# carrier.net
KiCad netlist of a schematic drawn in EAGLE
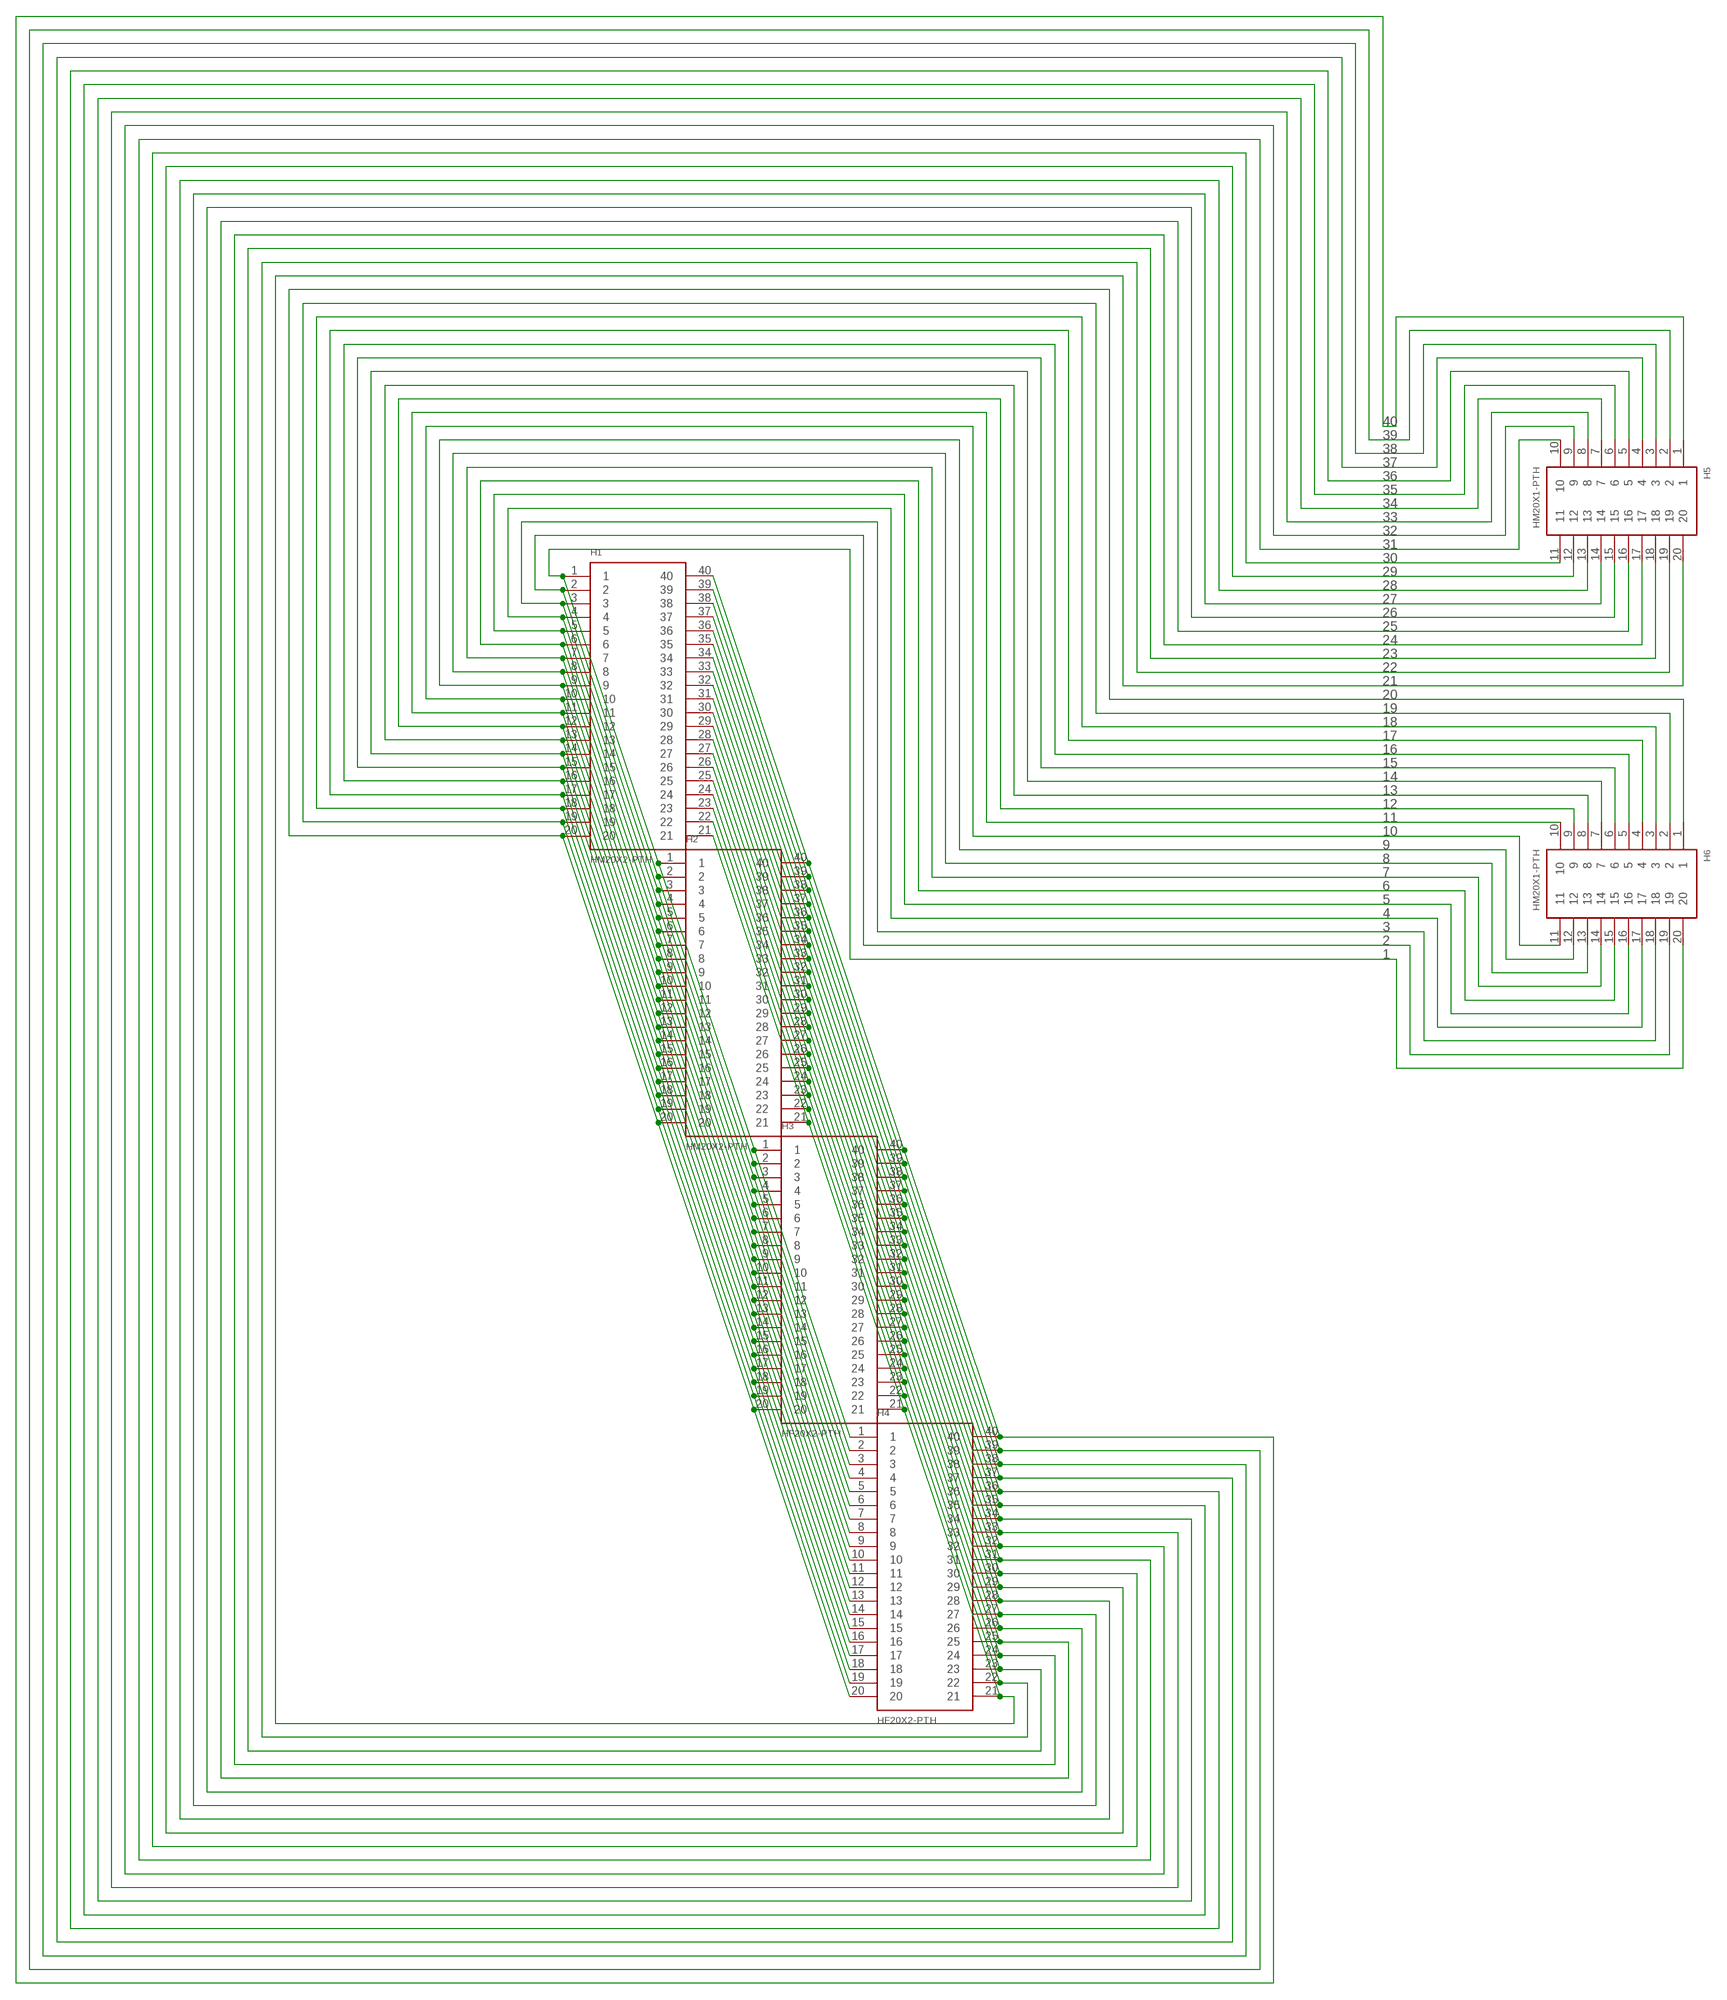
[diagram p0: schematic, sheet 1]

(export (version "E")
  (design (tool "Eeschema 10.0.6"))
  (components
    (comp (ref "H1")
      (value "HM20X2-PTH")
      (footprint "eagle-import:HM20X2-PTH")
      (libsource (lib "eagle-import") (part "HM20X2-PTH"))
    )
    (comp (ref "H2")
      (value "HM20X2-PTH")
      (footprint "eagle-import:HM20X2-PTH")
      (libsource (lib "eagle-import") (part "HM20X2-PTH"))
    )
    (comp (ref "H3")
      (value "HF20X2-PTH")
      (footprint "eagle-import:HF20X2-PTH")
      (libsource (lib "eagle-import") (part "HF20X2-PTH"))
    )
    (comp (ref "H4")
      (value "HF20X2-PTH")
      (footprint "eagle-import:HF20X2-PTH")
      (libsource (lib "eagle-import") (part "HF20X2-PTH"))
    )
    (comp (ref "H5")
      (value "HM20X1-PTH")
      (footprint "eagle-import:HM20X1-PTH")
      (libsource (lib "eagle-import") (part "HM20X1-PTH"))
    )
    (comp (ref "H6")
      (value "HM20X1-PTH")
      (footprint "eagle-import:HM20X1-PTH")
      (libsource (lib "eagle-import") (part "HM20X1-PTH"))
    )
  )
  (nets
    (net (code "1") (name "/1") (class "Default")
      (node (ref "H1") (pin "1") (pinfunction "1_1") (pintype "passive"))
      (node (ref "H2") (pin "1") (pinfunction "1_1") (pintype "passive"))
      (node (ref "H3") (pin "1") (pinfunction "1_1") (pintype "passive"))
      (node (ref "H4") (pin "1") (pinfunction "1_1") (pintype "passive"))
      (node (ref "H6") (pin "20") (pinfunction "20_20") (pintype "bidirectional"))
    )
    (net (code "2") (name "/2") (class "Default")
      (node (ref "H1") (pin "2") (pinfunction "2_2") (pintype "passive"))
      (node (ref "H2") (pin "2") (pinfunction "2_2") (pintype "passive"))
      (node (ref "H3") (pin "2") (pinfunction "2_2") (pintype "passive"))
      (node (ref "H4") (pin "2") (pinfunction "2_2") (pintype "passive"))
      (node (ref "H6") (pin "19") (pinfunction "19_19") (pintype "bidirectional"))
    )
    (net (code "3") (name "/3") (class "Default")
      (node (ref "H1") (pin "3") (pinfunction "3_3") (pintype "passive"))
      (node (ref "H2") (pin "3") (pinfunction "3_3") (pintype "passive"))
      (node (ref "H3") (pin "3") (pinfunction "3_3") (pintype "passive"))
      (node (ref "H4") (pin "3") (pinfunction "3_3") (pintype "passive"))
      (node (ref "H6") (pin "18") (pinfunction "18_18") (pintype "bidirectional"))
    )
    (net (code "4") (name "/4") (class "Default")
      (node (ref "H1") (pin "4") (pinfunction "4_4") (pintype "passive"))
      (node (ref "H2") (pin "4") (pinfunction "4_4") (pintype "passive"))
      (node (ref "H3") (pin "4") (pinfunction "4_4") (pintype "passive"))
      (node (ref "H4") (pin "4") (pinfunction "4_4") (pintype "passive"))
      (node (ref "H6") (pin "17") (pinfunction "17_17") (pintype "bidirectional"))
    )
    (net (code "5") (name "/5") (class "Default")
      (node (ref "H1") (pin "5") (pinfunction "5_5") (pintype "passive"))
      (node (ref "H2") (pin "5") (pinfunction "5_5") (pintype "passive"))
      (node (ref "H3") (pin "5") (pinfunction "5_5") (pintype "passive"))
      (node (ref "H4") (pin "5") (pinfunction "5_5") (pintype "passive"))
      (node (ref "H6") (pin "16") (pinfunction "16_16") (pintype "bidirectional"))
    )
    (net (code "6") (name "/6") (class "Default")
      (node (ref "H1") (pin "6") (pinfunction "6_6") (pintype "passive"))
      (node (ref "H2") (pin "6") (pinfunction "6_6") (pintype "passive"))
      (node (ref "H3") (pin "6") (pinfunction "6_6") (pintype "passive"))
      (node (ref "H4") (pin "6") (pinfunction "6_6") (pintype "passive"))
      (node (ref "H6") (pin "15") (pinfunction "15_15") (pintype "bidirectional"))
    )
    (net (code "7") (name "/7") (class "Default")
      (node (ref "H1") (pin "7") (pinfunction "7_7") (pintype "passive"))
      (node (ref "H2") (pin "7") (pinfunction "7_7") (pintype "passive"))
      (node (ref "H3") (pin "7") (pinfunction "7_7") (pintype "passive"))
      (node (ref "H4") (pin "7") (pinfunction "7_7") (pintype "passive"))
      (node (ref "H6") (pin "14") (pinfunction "14_14") (pintype "bidirectional"))
    )
    (net (code "8") (name "/8") (class "Default")
      (node (ref "H1") (pin "8") (pinfunction "8_8") (pintype "passive"))
      (node (ref "H2") (pin "8") (pinfunction "8_8") (pintype "passive"))
      (node (ref "H3") (pin "8") (pinfunction "8_8") (pintype "passive"))
      (node (ref "H4") (pin "8") (pinfunction "8_8") (pintype "passive"))
      (node (ref "H6") (pin "13") (pinfunction "13_13") (pintype "bidirectional"))
    )
    (net (code "9") (name "/9") (class "Default")
      (node (ref "H1") (pin "9") (pinfunction "9_9") (pintype "passive"))
      (node (ref "H2") (pin "9") (pinfunction "9_9") (pintype "passive"))
      (node (ref "H3") (pin "9") (pinfunction "9_9") (pintype "passive"))
      (node (ref "H4") (pin "9") (pinfunction "9_9") (pintype "passive"))
      (node (ref "H6") (pin "12") (pinfunction "12_12") (pintype "bidirectional"))
    )
    (net (code "10") (name "/10") (class "Default")
      (node (ref "H1") (pin "10") (pinfunction "10_10") (pintype "passive"))
      (node (ref "H2") (pin "10") (pinfunction "10_10") (pintype "passive"))
      (node (ref "H3") (pin "10") (pinfunction "10_10") (pintype "passive"))
      (node (ref "H4") (pin "10") (pinfunction "10_10") (pintype "passive"))
      (node (ref "H6") (pin "11") (pinfunction "11_11") (pintype "bidirectional"))
    )
    (net (code "11") (name "/11") (class "Default")
      (node (ref "H1") (pin "11") (pinfunction "11_11") (pintype "passive"))
      (node (ref "H2") (pin "11") (pinfunction "11_11") (pintype "passive"))
      (node (ref "H3") (pin "11") (pinfunction "11_11") (pintype "passive"))
      (node (ref "H4") (pin "11") (pinfunction "11_11") (pintype "passive"))
      (node (ref "H6") (pin "10") (pinfunction "10_10") (pintype "bidirectional"))
    )
    (net (code "12") (name "/12") (class "Default")
      (node (ref "H1") (pin "12") (pinfunction "12_12") (pintype "passive"))
      (node (ref "H2") (pin "12") (pinfunction "12_12") (pintype "passive"))
      (node (ref "H3") (pin "12") (pinfunction "12_12") (pintype "passive"))
      (node (ref "H4") (pin "12") (pinfunction "12_12") (pintype "passive"))
      (node (ref "H6") (pin "9") (pinfunction "9_9") (pintype "bidirectional"))
    )
    (net (code "13") (name "/13") (class "Default")
      (node (ref "H1") (pin "13") (pinfunction "13_13") (pintype "passive"))
      (node (ref "H2") (pin "13") (pinfunction "13_13") (pintype "passive"))
      (node (ref "H3") (pin "13") (pinfunction "13_13") (pintype "passive"))
      (node (ref "H4") (pin "13") (pinfunction "13_13") (pintype "passive"))
      (node (ref "H6") (pin "8") (pinfunction "8_8") (pintype "bidirectional"))
    )
    (net (code "14") (name "/14") (class "Default")
      (node (ref "H1") (pin "14") (pinfunction "14_14") (pintype "passive"))
      (node (ref "H2") (pin "14") (pinfunction "14_14") (pintype "passive"))
      (node (ref "H3") (pin "14") (pinfunction "14_14") (pintype "passive"))
      (node (ref "H4") (pin "14") (pinfunction "14_14") (pintype "passive"))
      (node (ref "H6") (pin "7") (pinfunction "7_7") (pintype "bidirectional"))
    )
    (net (code "15") (name "/15") (class "Default")
      (node (ref "H1") (pin "15") (pinfunction "15_15") (pintype "passive"))
      (node (ref "H2") (pin "15") (pinfunction "15_15") (pintype "passive"))
      (node (ref "H3") (pin "15") (pinfunction "15_15") (pintype "passive"))
      (node (ref "H4") (pin "15") (pinfunction "15_15") (pintype "passive"))
      (node (ref "H6") (pin "6") (pinfunction "6_6") (pintype "bidirectional"))
    )
    (net (code "16") (name "/16") (class "Default")
      (node (ref "H1") (pin "16") (pinfunction "16_16") (pintype "passive"))
      (node (ref "H2") (pin "16") (pinfunction "16_16") (pintype "passive"))
      (node (ref "H3") (pin "16") (pinfunction "16_16") (pintype "passive"))
      (node (ref "H4") (pin "16") (pinfunction "16_16") (pintype "passive"))
      (node (ref "H6") (pin "5") (pinfunction "5_5") (pintype "bidirectional"))
    )
    (net (code "17") (name "/17") (class "Default")
      (node (ref "H1") (pin "17") (pinfunction "17_17") (pintype "passive"))
      (node (ref "H2") (pin "17") (pinfunction "17_17") (pintype "passive"))
      (node (ref "H3") (pin "17") (pinfunction "17_17") (pintype "passive"))
      (node (ref "H4") (pin "17") (pinfunction "17_17") (pintype "passive"))
      (node (ref "H6") (pin "4") (pinfunction "4_4") (pintype "bidirectional"))
    )
    (net (code "18") (name "/18") (class "Default")
      (node (ref "H1") (pin "18") (pinfunction "18_18") (pintype "passive"))
      (node (ref "H2") (pin "18") (pinfunction "18_18") (pintype "passive"))
      (node (ref "H3") (pin "18") (pinfunction "18_18") (pintype "passive"))
      (node (ref "H4") (pin "18") (pinfunction "18_18") (pintype "passive"))
      (node (ref "H6") (pin "3") (pinfunction "3_3") (pintype "bidirectional"))
    )
    (net (code "19") (name "/19") (class "Default")
      (node (ref "H1") (pin "19") (pinfunction "19_19") (pintype "passive"))
      (node (ref "H2") (pin "19") (pinfunction "19_19") (pintype "passive"))
      (node (ref "H3") (pin "19") (pinfunction "19_19") (pintype "passive"))
      (node (ref "H4") (pin "19") (pinfunction "19_19") (pintype "passive"))
      (node (ref "H6") (pin "2") (pinfunction "2_2") (pintype "bidirectional"))
    )
    (net (code "20") (name "/20") (class "Default")
      (node (ref "H1") (pin "20") (pinfunction "20_20") (pintype "passive"))
      (node (ref "H2") (pin "20") (pinfunction "20_20") (pintype "passive"))
      (node (ref "H3") (pin "20") (pinfunction "20_20") (pintype "passive"))
      (node (ref "H4") (pin "20") (pinfunction "20_20") (pintype "passive"))
      (node (ref "H6") (pin "1") (pinfunction "1_1") (pintype "bidirectional"))
    )
    (net (code "21") (name "/21") (class "Default")
      (node (ref "H1") (pin "21") (pinfunction "21_21") (pintype "passive"))
      (node (ref "H2") (pin "21") (pinfunction "21_21") (pintype "passive"))
      (node (ref "H3") (pin "21") (pinfunction "21_21") (pintype "passive"))
      (node (ref "H4") (pin "21") (pinfunction "21_21") (pintype "passive"))
      (node (ref "H5") (pin "20") (pinfunction "20_20") (pintype "bidirectional"))
    )
    (net (code "22") (name "/22") (class "Default")
      (node (ref "H1") (pin "22") (pinfunction "22_22") (pintype "passive"))
      (node (ref "H2") (pin "22") (pinfunction "22_22") (pintype "passive"))
      (node (ref "H3") (pin "22") (pinfunction "22_22") (pintype "passive"))
      (node (ref "H4") (pin "22") (pinfunction "22_22") (pintype "passive"))
      (node (ref "H5") (pin "19") (pinfunction "19_19") (pintype "bidirectional"))
    )
    (net (code "23") (name "/23") (class "Default")
      (node (ref "H1") (pin "23") (pinfunction "23_23") (pintype "passive"))
      (node (ref "H2") (pin "23") (pinfunction "23_23") (pintype "passive"))
      (node (ref "H3") (pin "23") (pinfunction "23_23") (pintype "passive"))
      (node (ref "H4") (pin "23") (pinfunction "23_23") (pintype "passive"))
      (node (ref "H5") (pin "18") (pinfunction "18_18") (pintype "bidirectional"))
    )
    (net (code "24") (name "/24") (class "Default")
      (node (ref "H1") (pin "24") (pinfunction "24_24") (pintype "passive"))
      (node (ref "H2") (pin "24") (pinfunction "24_24") (pintype "passive"))
      (node (ref "H3") (pin "24") (pinfunction "24_24") (pintype "passive"))
      (node (ref "H4") (pin "24") (pinfunction "24_24") (pintype "passive"))
      (node (ref "H5") (pin "17") (pinfunction "17_17") (pintype "bidirectional"))
    )
    (net (code "25") (name "/25") (class "Default")
      (node (ref "H1") (pin "25") (pinfunction "25_25") (pintype "passive"))
      (node (ref "H2") (pin "25") (pinfunction "25_25") (pintype "passive"))
      (node (ref "H3") (pin "25") (pinfunction "25_25") (pintype "passive"))
      (node (ref "H4") (pin "25") (pinfunction "25_25") (pintype "passive"))
      (node (ref "H5") (pin "16") (pinfunction "16_16") (pintype "bidirectional"))
    )
    (net (code "26") (name "/26") (class "Default")
      (node (ref "H1") (pin "26") (pinfunction "26_26") (pintype "passive"))
      (node (ref "H2") (pin "26") (pinfunction "26_26") (pintype "passive"))
      (node (ref "H3") (pin "26") (pinfunction "26_26") (pintype "passive"))
      (node (ref "H4") (pin "26") (pinfunction "26_26") (pintype "passive"))
      (node (ref "H5") (pin "15") (pinfunction "15_15") (pintype "bidirectional"))
    )
    (net (code "27") (name "/27") (class "Default")
      (node (ref "H1") (pin "27") (pinfunction "27_27") (pintype "passive"))
      (node (ref "H2") (pin "27") (pinfunction "27_27") (pintype "passive"))
      (node (ref "H3") (pin "27") (pinfunction "27_27") (pintype "passive"))
      (node (ref "H4") (pin "27") (pinfunction "27_27") (pintype "passive"))
      (node (ref "H5") (pin "14") (pinfunction "14_14") (pintype "bidirectional"))
    )
    (net (code "28") (name "/28") (class "Default")
      (node (ref "H1") (pin "28") (pinfunction "28_28") (pintype "passive"))
      (node (ref "H2") (pin "28") (pinfunction "28_28") (pintype "passive"))
      (node (ref "H3") (pin "28") (pinfunction "28_28") (pintype "passive"))
      (node (ref "H4") (pin "28") (pinfunction "28_28") (pintype "passive"))
      (node (ref "H5") (pin "13") (pinfunction "13_13") (pintype "bidirectional"))
    )
    (net (code "29") (name "/29") (class "Default")
      (node (ref "H1") (pin "29") (pinfunction "29_29") (pintype "passive"))
      (node (ref "H2") (pin "29") (pinfunction "29_29") (pintype "passive"))
      (node (ref "H3") (pin "29") (pinfunction "29_29") (pintype "passive"))
      (node (ref "H4") (pin "29") (pinfunction "29_29") (pintype "passive"))
      (node (ref "H5") (pin "12") (pinfunction "12_12") (pintype "bidirectional"))
    )
    (net (code "30") (name "/30") (class "Default")
      (node (ref "H1") (pin "30") (pinfunction "30_30") (pintype "passive"))
      (node (ref "H2") (pin "30") (pinfunction "30_30") (pintype "passive"))
      (node (ref "H3") (pin "30") (pinfunction "30_30") (pintype "passive"))
      (node (ref "H4") (pin "30") (pinfunction "30_30") (pintype "passive"))
      (node (ref "H5") (pin "11") (pinfunction "11_11") (pintype "bidirectional"))
    )
    (net (code "31") (name "/31") (class "Default")
      (node (ref "H1") (pin "31") (pinfunction "31_31") (pintype "passive"))
      (node (ref "H2") (pin "31") (pinfunction "31_31") (pintype "passive"))
      (node (ref "H3") (pin "31") (pinfunction "31_31") (pintype "passive"))
      (node (ref "H4") (pin "31") (pinfunction "31_31") (pintype "passive"))
      (node (ref "H5") (pin "10") (pinfunction "10_10") (pintype "bidirectional"))
    )
    (net (code "32") (name "/32") (class "Default")
      (node (ref "H1") (pin "32") (pinfunction "32_32") (pintype "passive"))
      (node (ref "H2") (pin "32") (pinfunction "32_32") (pintype "passive"))
      (node (ref "H3") (pin "32") (pinfunction "32_32") (pintype "passive"))
      (node (ref "H4") (pin "32") (pinfunction "32_32") (pintype "passive"))
      (node (ref "H5") (pin "9") (pinfunction "9_9") (pintype "bidirectional"))
    )
    (net (code "33") (name "/33") (class "Default")
      (node (ref "H1") (pin "33") (pinfunction "33_33") (pintype "passive"))
      (node (ref "H2") (pin "33") (pinfunction "33_33") (pintype "passive"))
      (node (ref "H3") (pin "33") (pinfunction "33_33") (pintype "passive"))
      (node (ref "H4") (pin "33") (pinfunction "33_33") (pintype "passive"))
      (node (ref "H5") (pin "8") (pinfunction "8_8") (pintype "bidirectional"))
    )
    (net (code "34") (name "/34") (class "Default")
      (node (ref "H1") (pin "34") (pinfunction "34_34") (pintype "passive"))
      (node (ref "H2") (pin "34") (pinfunction "34_34") (pintype "passive"))
      (node (ref "H3") (pin "34") (pinfunction "34_34") (pintype "passive"))
      (node (ref "H4") (pin "34") (pinfunction "34_34") (pintype "passive"))
      (node (ref "H5") (pin "7") (pinfunction "7_7") (pintype "bidirectional"))
    )
    (net (code "35") (name "/35") (class "Default")
      (node (ref "H1") (pin "35") (pinfunction "35_35") (pintype "passive"))
      (node (ref "H2") (pin "35") (pinfunction "35_35") (pintype "passive"))
      (node (ref "H3") (pin "35") (pinfunction "35_35") (pintype "passive"))
      (node (ref "H4") (pin "35") (pinfunction "35_35") (pintype "passive"))
      (node (ref "H5") (pin "6") (pinfunction "6_6") (pintype "bidirectional"))
    )
    (net (code "36") (name "/36") (class "Default")
      (node (ref "H1") (pin "36") (pinfunction "36_36") (pintype "passive"))
      (node (ref "H2") (pin "36") (pinfunction "36_36") (pintype "passive"))
      (node (ref "H3") (pin "36") (pinfunction "36_36") (pintype "passive"))
      (node (ref "H4") (pin "36") (pinfunction "36_36") (pintype "passive"))
      (node (ref "H5") (pin "5") (pinfunction "5_5") (pintype "bidirectional"))
    )
    (net (code "37") (name "/37") (class "Default")
      (node (ref "H1") (pin "37") (pinfunction "37_37") (pintype "passive"))
      (node (ref "H2") (pin "37") (pinfunction "37_37") (pintype "passive"))
      (node (ref "H3") (pin "37") (pinfunction "37_37") (pintype "passive"))
      (node (ref "H4") (pin "37") (pinfunction "37_37") (pintype "passive"))
      (node (ref "H5") (pin "4") (pinfunction "4_4") (pintype "bidirectional"))
    )
    (net (code "38") (name "/38") (class "Default")
      (node (ref "H1") (pin "38") (pinfunction "38_38") (pintype "passive"))
      (node (ref "H2") (pin "38") (pinfunction "38_38") (pintype "passive"))
      (node (ref "H3") (pin "38") (pinfunction "38_38") (pintype "passive"))
      (node (ref "H4") (pin "38") (pinfunction "38_38") (pintype "passive"))
      (node (ref "H5") (pin "3") (pinfunction "3_3") (pintype "bidirectional"))
    )
    (net (code "39") (name "/39") (class "Default")
      (node (ref "H1") (pin "39") (pinfunction "39_39") (pintype "passive"))
      (node (ref "H2") (pin "39") (pinfunction "39_39") (pintype "passive"))
      (node (ref "H3") (pin "39") (pinfunction "39_39") (pintype "passive"))
      (node (ref "H4") (pin "39") (pinfunction "39_39") (pintype "passive"))
      (node (ref "H5") (pin "2") (pinfunction "2_2") (pintype "bidirectional"))
    )
    (net (code "40") (name "/40") (class "Default")
      (node (ref "H1") (pin "40") (pinfunction "40_40") (pintype "passive"))
      (node (ref "H2") (pin "40") (pinfunction "40_40") (pintype "passive"))
      (node (ref "H3") (pin "40") (pinfunction "40_40") (pintype "passive"))
      (node (ref "H4") (pin "40") (pinfunction "40_40") (pintype "passive"))
      (node (ref "H5") (pin "1") (pinfunction "1_1") (pintype "bidirectional"))
    )
  )
)
